# Arranged_in_Fusion.net
KiCad netlist of a schematic drawn in EAGLE
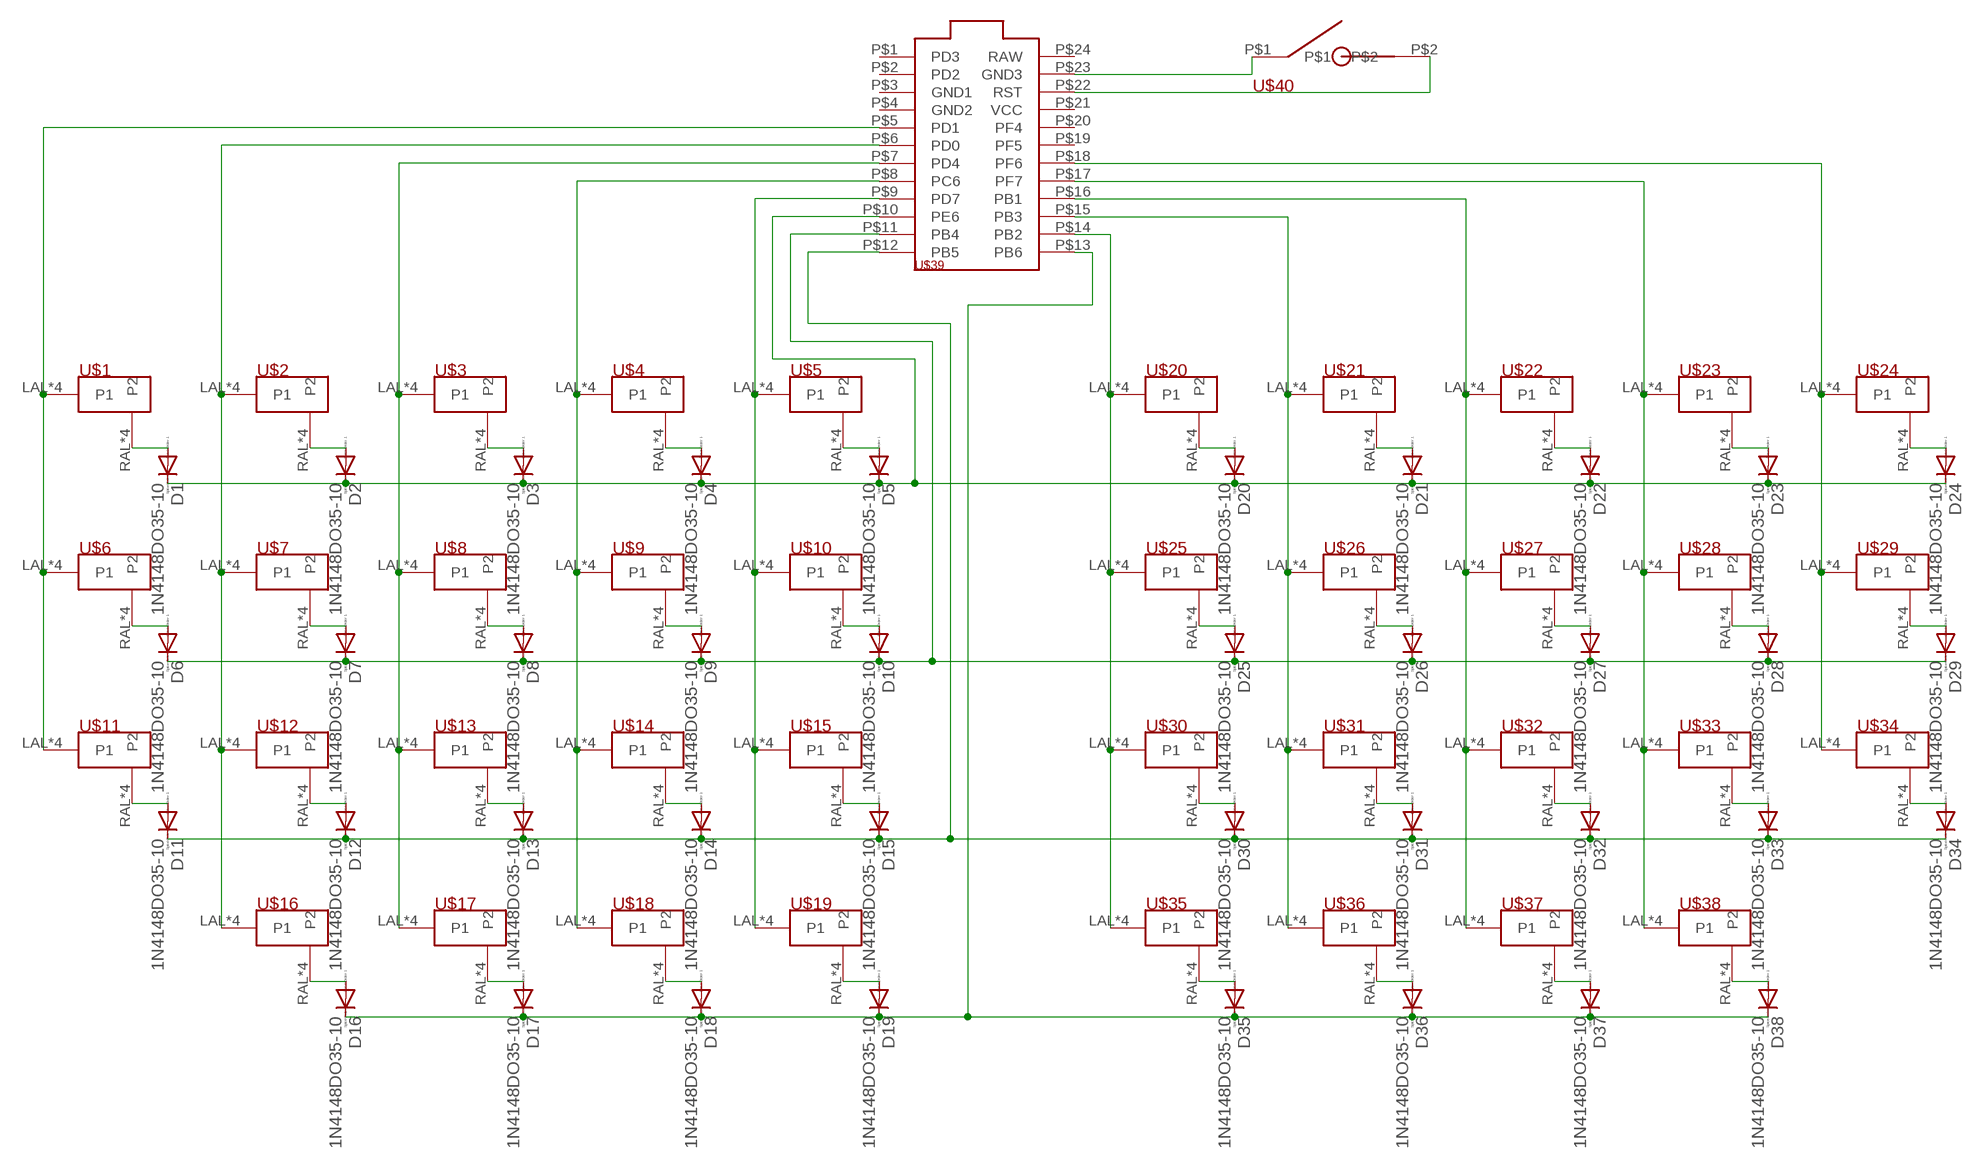
[diagram p0: schematic, sheet 1]

(export (version "E")
  (design (tool "Eeschema 10.0.6"))
  (components
    (comp (ref "D1")
      (value "1N4148DO35-10")
      (footprint "eagle-import:DO35-10")
      (libsource (lib "eagle-import") (part "1N4148DO35-10"))
    )
    (comp (ref "D2")
      (value "1N4148DO35-10")
      (footprint "eagle-import:DO35-10")
      (libsource (lib "eagle-import") (part "1N4148DO35-10"))
    )
    (comp (ref "D3")
      (value "1N4148DO35-10")
      (footprint "eagle-import:DO35-10")
      (libsource (lib "eagle-import") (part "1N4148DO35-10"))
    )
    (comp (ref "D4")
      (value "1N4148DO35-10")
      (footprint "eagle-import:DO35-10")
      (libsource (lib "eagle-import") (part "1N4148DO35-10"))
    )
    (comp (ref "D5")
      (value "1N4148DO35-10")
      (footprint "eagle-import:DO35-10")
      (libsource (lib "eagle-import") (part "1N4148DO35-10"))
    )
    (comp (ref "D6")
      (value "1N4148DO35-10")
      (footprint "eagle-import:DO35-10")
      (libsource (lib "eagle-import") (part "1N4148DO35-10"))
    )
    (comp (ref "D7")
      (value "1N4148DO35-10")
      (footprint "eagle-import:DO35-10")
      (libsource (lib "eagle-import") (part "1N4148DO35-10"))
    )
    (comp (ref "D8")
      (value "1N4148DO35-10")
      (footprint "eagle-import:DO35-10")
      (libsource (lib "eagle-import") (part "1N4148DO35-10"))
    )
    (comp (ref "D9")
      (value "1N4148DO35-10")
      (footprint "eagle-import:DO35-10")
      (libsource (lib "eagle-import") (part "1N4148DO35-10"))
    )
    (comp (ref "D10")
      (value "1N4148DO35-10")
      (footprint "eagle-import:DO35-10")
      (libsource (lib "eagle-import") (part "1N4148DO35-10"))
    )
    (comp (ref "D11")
      (value "1N4148DO35-10")
      (footprint "eagle-import:DO35-10")
      (libsource (lib "eagle-import") (part "1N4148DO35-10"))
    )
    (comp (ref "D12")
      (value "1N4148DO35-10")
      (footprint "eagle-import:DO35-10")
      (libsource (lib "eagle-import") (part "1N4148DO35-10"))
    )
    (comp (ref "D13")
      (value "1N4148DO35-10")
      (footprint "eagle-import:DO35-10")
      (libsource (lib "eagle-import") (part "1N4148DO35-10"))
    )
    (comp (ref "D14")
      (value "1N4148DO35-10")
      (footprint "eagle-import:DO35-10")
      (libsource (lib "eagle-import") (part "1N4148DO35-10"))
    )
    (comp (ref "D15")
      (value "1N4148DO35-10")
      (footprint "eagle-import:DO35-10")
      (libsource (lib "eagle-import") (part "1N4148DO35-10"))
    )
    (comp (ref "D16")
      (value "1N4148DO35-10")
      (footprint "eagle-import:DO35-10")
      (libsource (lib "eagle-import") (part "1N4148DO35-10"))
    )
    (comp (ref "D17")
      (value "1N4148DO35-10")
      (footprint "eagle-import:DO35-10")
      (libsource (lib "eagle-import") (part "1N4148DO35-10"))
    )
    (comp (ref "D18")
      (value "1N4148DO35-10")
      (footprint "eagle-import:DO35-10")
      (libsource (lib "eagle-import") (part "1N4148DO35-10"))
    )
    (comp (ref "D19")
      (value "1N4148DO35-10")
      (footprint "eagle-import:DO35-10")
      (libsource (lib "eagle-import") (part "1N4148DO35-10"))
    )
    (comp (ref "D20")
      (value "1N4148DO35-10")
      (footprint "eagle-import:DO35-10")
      (libsource (lib "eagle-import") (part "1N4148DO35-10"))
    )
    (comp (ref "D21")
      (value "1N4148DO35-10")
      (footprint "eagle-import:DO35-10")
      (libsource (lib "eagle-import") (part "1N4148DO35-10"))
    )
    (comp (ref "D22")
      (value "1N4148DO35-10")
      (footprint "eagle-import:DO35-10")
      (libsource (lib "eagle-import") (part "1N4148DO35-10"))
    )
    (comp (ref "D23")
      (value "1N4148DO35-10")
      (footprint "eagle-import:DO35-10")
      (libsource (lib "eagle-import") (part "1N4148DO35-10"))
    )
    (comp (ref "D24")
      (value "1N4148DO35-10")
      (footprint "eagle-import:DO35-10")
      (libsource (lib "eagle-import") (part "1N4148DO35-10"))
    )
    (comp (ref "D25")
      (value "1N4148DO35-10")
      (footprint "eagle-import:DO35-10")
      (libsource (lib "eagle-import") (part "1N4148DO35-10"))
    )
    (comp (ref "D26")
      (value "1N4148DO35-10")
      (footprint "eagle-import:DO35-10")
      (libsource (lib "eagle-import") (part "1N4148DO35-10"))
    )
    (comp (ref "D27")
      (value "1N4148DO35-10")
      (footprint "eagle-import:DO35-10")
      (libsource (lib "eagle-import") (part "1N4148DO35-10"))
    )
    (comp (ref "D28")
      (value "1N4148DO35-10")
      (footprint "eagle-import:DO35-10")
      (libsource (lib "eagle-import") (part "1N4148DO35-10"))
    )
    (comp (ref "D29")
      (value "1N4148DO35-10")
      (footprint "eagle-import:DO35-10")
      (libsource (lib "eagle-import") (part "1N4148DO35-10"))
    )
    (comp (ref "D30")
      (value "1N4148DO35-10")
      (footprint "eagle-import:DO35-10")
      (libsource (lib "eagle-import") (part "1N4148DO35-10"))
    )
    (comp (ref "D31")
      (value "1N4148DO35-10")
      (footprint "eagle-import:DO35-10")
      (libsource (lib "eagle-import") (part "1N4148DO35-10"))
    )
    (comp (ref "D32")
      (value "1N4148DO35-10")
      (footprint "eagle-import:DO35-10")
      (libsource (lib "eagle-import") (part "1N4148DO35-10"))
    )
    (comp (ref "D33")
      (value "1N4148DO35-10")
      (footprint "eagle-import:DO35-10")
      (libsource (lib "eagle-import") (part "1N4148DO35-10"))
    )
    (comp (ref "D34")
      (value "1N4148DO35-10")
      (footprint "eagle-import:DO35-10")
      (libsource (lib "eagle-import") (part "1N4148DO35-10"))
    )
    (comp (ref "D35")
      (value "1N4148DO35-10")
      (footprint "eagle-import:DO35-10")
      (libsource (lib "eagle-import") (part "1N4148DO35-10"))
    )
    (comp (ref "D36")
      (value "1N4148DO35-10")
      (footprint "eagle-import:DO35-10")
      (libsource (lib "eagle-import") (part "1N4148DO35-10"))
    )
    (comp (ref "D37")
      (value "1N4148DO35-10")
      (footprint "eagle-import:DO35-10")
      (libsource (lib "eagle-import") (part "1N4148DO35-10"))
    )
    (comp (ref "D38")
      (value "1N4148DO35-10")
      (footprint "eagle-import:DO35-10")
      (libsource (lib "eagle-import") (part "1N4148DO35-10"))
    )
    (comp (ref "U$1")
      (value "MANDOUBLEONESIDED")
      (footprint "eagle-import:MX_ALPS")
      (libsource (lib "eagle-import") (part "MANDOUBLEONESIDED"))
    )
    (comp (ref "U$2")
      (value "MANDOUBLEONESIDED")
      (footprint "eagle-import:MX_ALPS")
      (libsource (lib "eagle-import") (part "MANDOUBLEONESIDED"))
    )
    (comp (ref "U$3")
      (value "MANDOUBLEONESIDED")
      (footprint "eagle-import:MX_ALPS")
      (libsource (lib "eagle-import") (part "MANDOUBLEONESIDED"))
    )
    (comp (ref "U$4")
      (value "MANDOUBLEONESIDED")
      (footprint "eagle-import:MX_ALPS")
      (libsource (lib "eagle-import") (part "MANDOUBLEONESIDED"))
    )
    (comp (ref "U$5")
      (value "MANDOUBLEONESIDED")
      (footprint "eagle-import:MX_ALPS")
      (libsource (lib "eagle-import") (part "MANDOUBLEONESIDED"))
    )
    (comp (ref "U$6")
      (value "MANDOUBLEONESIDED")
      (footprint "eagle-import:MX_ALPS")
      (libsource (lib "eagle-import") (part "MANDOUBLEONESIDED"))
    )
    (comp (ref "U$7")
      (value "MANDOUBLEONESIDED")
      (footprint "eagle-import:MX_ALPS")
      (libsource (lib "eagle-import") (part "MANDOUBLEONESIDED"))
    )
    (comp (ref "U$8")
      (value "MANDOUBLEONESIDED")
      (footprint "eagle-import:MX_ALPS")
      (libsource (lib "eagle-import") (part "MANDOUBLEONESIDED"))
    )
    (comp (ref "U$9")
      (value "MANDOUBLEONESIDED")
      (footprint "eagle-import:MX_ALPS")
      (libsource (lib "eagle-import") (part "MANDOUBLEONESIDED"))
    )
    (comp (ref "U$10")
      (value "MANDOUBLEONESIDED")
      (footprint "eagle-import:MX_ALPS")
      (libsource (lib "eagle-import") (part "MANDOUBLEONESIDED"))
    )
    (comp (ref "U$11")
      (value "MANDOUBLEONESIDED")
      (footprint "eagle-import:MX_ALPS")
      (libsource (lib "eagle-import") (part "MANDOUBLEONESIDED"))
    )
    (comp (ref "U$12")
      (value "MANDOUBLEONESIDED")
      (footprint "eagle-import:MX_ALPS")
      (libsource (lib "eagle-import") (part "MANDOUBLEONESIDED"))
    )
    (comp (ref "U$13")
      (value "MANDOUBLEONESIDED")
      (footprint "eagle-import:MX_ALPS")
      (libsource (lib "eagle-import") (part "MANDOUBLEONESIDED"))
    )
    (comp (ref "U$14")
      (value "MANDOUBLEONESIDED")
      (footprint "eagle-import:MX_ALPS")
      (libsource (lib "eagle-import") (part "MANDOUBLEONESIDED"))
    )
    (comp (ref "U$15")
      (value "MANDOUBLEONESIDED")
      (footprint "eagle-import:MX_ALPS")
      (libsource (lib "eagle-import") (part "MANDOUBLEONESIDED"))
    )
    (comp (ref "U$16")
      (value "MANDOUBLEONESIDED")
      (footprint "eagle-import:MX_ALPS")
      (libsource (lib "eagle-import") (part "MANDOUBLEONESIDED"))
    )
    (comp (ref "U$17")
      (value "MANDOUBLEONESIDED")
      (footprint "eagle-import:MX_ALPS")
      (libsource (lib "eagle-import") (part "MANDOUBLEONESIDED"))
    )
    (comp (ref "U$18")
      (value "MANDOUBLEONESIDED")
      (footprint "eagle-import:MX_ALPS")
      (libsource (lib "eagle-import") (part "MANDOUBLEONESIDED"))
    )
    (comp (ref "U$19")
      (value "MANDOUBLEONESIDED")
      (footprint "eagle-import:MX_ALPS")
      (libsource (lib "eagle-import") (part "MANDOUBLEONESIDED"))
    )
    (comp (ref "U$20")
      (value "MANDOUBLEONESIDED")
      (footprint "eagle-import:MX_ALPS")
      (libsource (lib "eagle-import") (part "MANDOUBLEONESIDED"))
    )
    (comp (ref "U$21")
      (value "MANDOUBLEONESIDED")
      (footprint "eagle-import:MX_ALPS")
      (libsource (lib "eagle-import") (part "MANDOUBLEONESIDED"))
    )
    (comp (ref "U$22")
      (value "MANDOUBLEONESIDED")
      (footprint "eagle-import:MX_ALPS")
      (libsource (lib "eagle-import") (part "MANDOUBLEONESIDED"))
    )
    (comp (ref "U$23")
      (value "MANDOUBLEONESIDED")
      (footprint "eagle-import:MX_ALPS")
      (libsource (lib "eagle-import") (part "MANDOUBLEONESIDED"))
    )
    (comp (ref "U$24")
      (value "MANDOUBLEONESIDED")
      (footprint "eagle-import:MX_ALPS")
      (libsource (lib "eagle-import") (part "MANDOUBLEONESIDED"))
    )
    (comp (ref "U$25")
      (value "MANDOUBLEONESIDED")
      (footprint "eagle-import:MX_ALPS")
      (libsource (lib "eagle-import") (part "MANDOUBLEONESIDED"))
    )
    (comp (ref "U$26")
      (value "MANDOUBLEONESIDED")
      (footprint "eagle-import:MX_ALPS")
      (libsource (lib "eagle-import") (part "MANDOUBLEONESIDED"))
    )
    (comp (ref "U$27")
      (value "MANDOUBLEONESIDED")
      (footprint "eagle-import:MX_ALPS")
      (libsource (lib "eagle-import") (part "MANDOUBLEONESIDED"))
    )
    (comp (ref "U$28")
      (value "MANDOUBLEONESIDED")
      (footprint "eagle-import:MX_ALPS")
      (libsource (lib "eagle-import") (part "MANDOUBLEONESIDED"))
    )
    (comp (ref "U$29")
      (value "MANDOUBLEONESIDED")
      (footprint "eagle-import:MX_ALPS")
      (libsource (lib "eagle-import") (part "MANDOUBLEONESIDED"))
    )
    (comp (ref "U$30")
      (value "MANDOUBLEONESIDED")
      (footprint "eagle-import:MX_ALPS")
      (libsource (lib "eagle-import") (part "MANDOUBLEONESIDED"))
    )
    (comp (ref "U$31")
      (value "MANDOUBLEONESIDED")
      (footprint "eagle-import:MX_ALPS")
      (libsource (lib "eagle-import") (part "MANDOUBLEONESIDED"))
    )
    (comp (ref "U$32")
      (value "MANDOUBLEONESIDED")
      (footprint "eagle-import:MX_ALPS")
      (libsource (lib "eagle-import") (part "MANDOUBLEONESIDED"))
    )
    (comp (ref "U$33")
      (value "MANDOUBLEONESIDED")
      (footprint "eagle-import:MX_ALPS")
      (libsource (lib "eagle-import") (part "MANDOUBLEONESIDED"))
    )
    (comp (ref "U$34")
      (value "MANDOUBLEONESIDED")
      (footprint "eagle-import:MX_ALPS")
      (libsource (lib "eagle-import") (part "MANDOUBLEONESIDED"))
    )
    (comp (ref "U$35")
      (value "MANDOUBLEONESIDED")
      (footprint "eagle-import:MX_ALPS")
      (libsource (lib "eagle-import") (part "MANDOUBLEONESIDED"))
    )
    (comp (ref "U$36")
      (value "MANDOUBLEONESIDED")
      (footprint "eagle-import:MX_ALPS")
      (libsource (lib "eagle-import") (part "MANDOUBLEONESIDED"))
    )
    (comp (ref "U$37")
      (value "MANDOUBLEONESIDED")
      (footprint "eagle-import:MX_ALPS")
      (libsource (lib "eagle-import") (part "MANDOUBLEONESIDED"))
    )
    (comp (ref "U$38")
      (value "MANDOUBLEONESIDED")
      (footprint "eagle-import:MX_ALPS")
      (libsource (lib "eagle-import") (part "MANDOUBLEONESIDED"))
    )
    (comp (ref "U$39")
      (value "PROMICRO")
      (footprint "eagle-import:PROMICRO")
      (libsource (lib "eagle-import") (part "PROMICRO"))
    )
    (comp (ref "U$40")
      (value "RSTSW")
      (footprint "eagle-import:SKHL")
      (libsource (lib "eagle-import") (part "RSTSW"))
    )
  )
  (nets
    (net (code "1") (name "Net-(D1-PadA)") (class "Default")
      (node (ref "D1") (pin "A") (pinfunction "A_A") (pintype "passive"))
      (node (ref "U$1") (pin "RAL") (pinfunction "P2_RAL") (pintype "bidirectional"))
      (node (ref "U$1") (pin "RAR") (pinfunction "P2_RAR") (pintype "bidirectional"))
      (node (ref "U$1") (pin "RCL") (pinfunction "P2_RCL") (pintype "bidirectional"))
      (node (ref "U$1") (pin "RCR") (pinfunction "P2_RCR") (pintype "bidirectional"))
    )
    (net (code "2") (name "Net-(D2-PadA)") (class "Default")
      (node (ref "D2") (pin "A") (pinfunction "A_A") (pintype "passive"))
      (node (ref "U$2") (pin "RAL") (pinfunction "P2_RAL") (pintype "bidirectional"))
      (node (ref "U$2") (pin "RAR") (pinfunction "P2_RAR") (pintype "bidirectional"))
      (node (ref "U$2") (pin "RCL") (pinfunction "P2_RCL") (pintype "bidirectional"))
      (node (ref "U$2") (pin "RCR") (pinfunction "P2_RCR") (pintype "bidirectional"))
    )
    (net (code "3") (name "Net-(D3-PadA)") (class "Default")
      (node (ref "D3") (pin "A") (pinfunction "A_A") (pintype "passive"))
      (node (ref "U$3") (pin "RAL") (pinfunction "P2_RAL") (pintype "bidirectional"))
      (node (ref "U$3") (pin "RAR") (pinfunction "P2_RAR") (pintype "bidirectional"))
      (node (ref "U$3") (pin "RCL") (pinfunction "P2_RCL") (pintype "bidirectional"))
      (node (ref "U$3") (pin "RCR") (pinfunction "P2_RCR") (pintype "bidirectional"))
    )
    (net (code "4") (name "Net-(D4-PadA)") (class "Default")
      (node (ref "D4") (pin "A") (pinfunction "A_A") (pintype "passive"))
      (node (ref "U$4") (pin "RAL") (pinfunction "P2_RAL") (pintype "bidirectional"))
      (node (ref "U$4") (pin "RAR") (pinfunction "P2_RAR") (pintype "bidirectional"))
      (node (ref "U$4") (pin "RCL") (pinfunction "P2_RCL") (pintype "bidirectional"))
      (node (ref "U$4") (pin "RCR") (pinfunction "P2_RCR") (pintype "bidirectional"))
    )
    (net (code "5") (name "Net-(D5-PadA)") (class "Default")
      (node (ref "D5") (pin "A") (pinfunction "A_A") (pintype "passive"))
      (node (ref "U$5") (pin "RAL") (pinfunction "P2_RAL") (pintype "bidirectional"))
      (node (ref "U$5") (pin "RAR") (pinfunction "P2_RAR") (pintype "bidirectional"))
      (node (ref "U$5") (pin "RCL") (pinfunction "P2_RCL") (pintype "bidirectional"))
      (node (ref "U$5") (pin "RCR") (pinfunction "P2_RCR") (pintype "bidirectional"))
    )
    (net (code "6") (name "Net-(D6-PadA)") (class "Default")
      (node (ref "D6") (pin "A") (pinfunction "A_A") (pintype "passive"))
      (node (ref "U$6") (pin "RAL") (pinfunction "P2_RAL") (pintype "bidirectional"))
      (node (ref "U$6") (pin "RAR") (pinfunction "P2_RAR") (pintype "bidirectional"))
      (node (ref "U$6") (pin "RCL") (pinfunction "P2_RCL") (pintype "bidirectional"))
      (node (ref "U$6") (pin "RCR") (pinfunction "P2_RCR") (pintype "bidirectional"))
    )
    (net (code "7") (name "Net-(D7-PadA)") (class "Default")
      (node (ref "D7") (pin "A") (pinfunction "A_A") (pintype "passive"))
      (node (ref "U$7") (pin "RAL") (pinfunction "P2_RAL") (pintype "bidirectional"))
      (node (ref "U$7") (pin "RAR") (pinfunction "P2_RAR") (pintype "bidirectional"))
      (node (ref "U$7") (pin "RCL") (pinfunction "P2_RCL") (pintype "bidirectional"))
      (node (ref "U$7") (pin "RCR") (pinfunction "P2_RCR") (pintype "bidirectional"))
    )
    (net (code "8") (name "Net-(D8-PadA)") (class "Default")
      (node (ref "D8") (pin "A") (pinfunction "A_A") (pintype "passive"))
      (node (ref "U$8") (pin "RAL") (pinfunction "P2_RAL") (pintype "bidirectional"))
      (node (ref "U$8") (pin "RAR") (pinfunction "P2_RAR") (pintype "bidirectional"))
      (node (ref "U$8") (pin "RCL") (pinfunction "P2_RCL") (pintype "bidirectional"))
      (node (ref "U$8") (pin "RCR") (pinfunction "P2_RCR") (pintype "bidirectional"))
    )
    (net (code "9") (name "Net-(D9-PadA)") (class "Default")
      (node (ref "D9") (pin "A") (pinfunction "A_A") (pintype "passive"))
      (node (ref "U$9") (pin "RAL") (pinfunction "P2_RAL") (pintype "bidirectional"))
      (node (ref "U$9") (pin "RAR") (pinfunction "P2_RAR") (pintype "bidirectional"))
      (node (ref "U$9") (pin "RCL") (pinfunction "P2_RCL") (pintype "bidirectional"))
      (node (ref "U$9") (pin "RCR") (pinfunction "P2_RCR") (pintype "bidirectional"))
    )
    (net (code "10") (name "Net-(D10-PadA)") (class "Default")
      (node (ref "D10") (pin "A") (pinfunction "A_A") (pintype "passive"))
      (node (ref "U$10") (pin "RAL") (pinfunction "P2_RAL") (pintype "bidirectional"))
      (node (ref "U$10") (pin "RAR") (pinfunction "P2_RAR") (pintype "bidirectional"))
      (node (ref "U$10") (pin "RCL") (pinfunction "P2_RCL") (pintype "bidirectional"))
      (node (ref "U$10") (pin "RCR") (pinfunction "P2_RCR") (pintype "bidirectional"))
    )
    (net (code "11") (name "Net-(D11-PadA)") (class "Default")
      (node (ref "D11") (pin "A") (pinfunction "A_A") (pintype "passive"))
      (node (ref "U$11") (pin "RAL") (pinfunction "P2_RAL") (pintype "bidirectional"))
      (node (ref "U$11") (pin "RAR") (pinfunction "P2_RAR") (pintype "bidirectional"))
      (node (ref "U$11") (pin "RCL") (pinfunction "P2_RCL") (pintype "bidirectional"))
      (node (ref "U$11") (pin "RCR") (pinfunction "P2_RCR") (pintype "bidirectional"))
    )
    (net (code "12") (name "Net-(D12-PadA)") (class "Default")
      (node (ref "D12") (pin "A") (pinfunction "A_A") (pintype "passive"))
      (node (ref "U$12") (pin "RAL") (pinfunction "P2_RAL") (pintype "bidirectional"))
      (node (ref "U$12") (pin "RAR") (pinfunction "P2_RAR") (pintype "bidirectional"))
      (node (ref "U$12") (pin "RCL") (pinfunction "P2_RCL") (pintype "bidirectional"))
      (node (ref "U$12") (pin "RCR") (pinfunction "P2_RCR") (pintype "bidirectional"))
    )
    (net (code "13") (name "Net-(D13-PadA)") (class "Default")
      (node (ref "D13") (pin "A") (pinfunction "A_A") (pintype "passive"))
      (node (ref "U$13") (pin "RAL") (pinfunction "P2_RAL") (pintype "bidirectional"))
      (node (ref "U$13") (pin "RAR") (pinfunction "P2_RAR") (pintype "bidirectional"))
      (node (ref "U$13") (pin "RCL") (pinfunction "P2_RCL") (pintype "bidirectional"))
      (node (ref "U$13") (pin "RCR") (pinfunction "P2_RCR") (pintype "bidirectional"))
    )
    (net (code "14") (name "Net-(D14-PadA)") (class "Default")
      (node (ref "D14") (pin "A") (pinfunction "A_A") (pintype "passive"))
      (node (ref "U$14") (pin "RAL") (pinfunction "P2_RAL") (pintype "bidirectional"))
      (node (ref "U$14") (pin "RAR") (pinfunction "P2_RAR") (pintype "bidirectional"))
      (node (ref "U$14") (pin "RCL") (pinfunction "P2_RCL") (pintype "bidirectional"))
      (node (ref "U$14") (pin "RCR") (pinfunction "P2_RCR") (pintype "bidirectional"))
    )
    (net (code "15") (name "Net-(D15-PadA)") (class "Default")
      (node (ref "D15") (pin "A") (pinfunction "A_A") (pintype "passive"))
      (node (ref "U$15") (pin "RAL") (pinfunction "P2_RAL") (pintype "bidirectional"))
      (node (ref "U$15") (pin "RAR") (pinfunction "P2_RAR") (pintype "bidirectional"))
      (node (ref "U$15") (pin "RCL") (pinfunction "P2_RCL") (pintype "bidirectional"))
      (node (ref "U$15") (pin "RCR") (pinfunction "P2_RCR") (pintype "bidirectional"))
    )
    (net (code "16") (name "Net-(D16-PadA)") (class "Default")
      (node (ref "D16") (pin "A") (pinfunction "A_A") (pintype "passive"))
      (node (ref "U$16") (pin "RAL") (pinfunction "P2_RAL") (pintype "bidirectional"))
      (node (ref "U$16") (pin "RAR") (pinfunction "P2_RAR") (pintype "bidirectional"))
      (node (ref "U$16") (pin "RCL") (pinfunction "P2_RCL") (pintype "bidirectional"))
      (node (ref "U$16") (pin "RCR") (pinfunction "P2_RCR") (pintype "bidirectional"))
    )
    (net (code "17") (name "Net-(D17-PadA)") (class "Default")
      (node (ref "D17") (pin "A") (pinfunction "A_A") (pintype "passive"))
      (node (ref "U$17") (pin "RAL") (pinfunction "P2_RAL") (pintype "bidirectional"))
      (node (ref "U$17") (pin "RAR") (pinfunction "P2_RAR") (pintype "bidirectional"))
      (node (ref "U$17") (pin "RCL") (pinfunction "P2_RCL") (pintype "bidirectional"))
      (node (ref "U$17") (pin "RCR") (pinfunction "P2_RCR") (pintype "bidirectional"))
    )
    (net (code "18") (name "Net-(D18-PadA)") (class "Default")
      (node (ref "D18") (pin "A") (pinfunction "A_A") (pintype "passive"))
      (node (ref "U$18") (pin "RAL") (pinfunction "P2_RAL") (pintype "bidirectional"))
      (node (ref "U$18") (pin "RAR") (pinfunction "P2_RAR") (pintype "bidirectional"))
      (node (ref "U$18") (pin "RCL") (pinfunction "P2_RCL") (pintype "bidirectional"))
      (node (ref "U$18") (pin "RCR") (pinfunction "P2_RCR") (pintype "bidirectional"))
    )
    (net (code "19") (name "Net-(D19-PadA)") (class "Default")
      (node (ref "D19") (pin "A") (pinfunction "A_A") (pintype "passive"))
      (node (ref "U$19") (pin "RAL") (pinfunction "P2_RAL") (pintype "bidirectional"))
      (node (ref "U$19") (pin "RAR") (pinfunction "P2_RAR") (pintype "bidirectional"))
      (node (ref "U$19") (pin "RCL") (pinfunction "P2_RCL") (pintype "bidirectional"))
      (node (ref "U$19") (pin "RCR") (pinfunction "P2_RCR") (pintype "bidirectional"))
    )
    (net (code "20") (name "Net-(D20-PadA)") (class "Default")
      (node (ref "D20") (pin "A") (pinfunction "A_A") (pintype "passive"))
      (node (ref "U$20") (pin "RAL") (pinfunction "P2_RAL") (pintype "bidirectional"))
      (node (ref "U$20") (pin "RAR") (pinfunction "P2_RAR") (pintype "bidirectional"))
      (node (ref "U$20") (pin "RCL") (pinfunction "P2_RCL") (pintype "bidirectional"))
      (node (ref "U$20") (pin "RCR") (pinfunction "P2_RCR") (pintype "bidirectional"))
    )
    (net (code "21") (name "Net-(D21-PadA)") (class "Default")
      (node (ref "D21") (pin "A") (pinfunction "A_A") (pintype "passive"))
      (node (ref "U$21") (pin "RAL") (pinfunction "P2_RAL") (pintype "bidirectional"))
      (node (ref "U$21") (pin "RAR") (pinfunction "P2_RAR") (pintype "bidirectional"))
      (node (ref "U$21") (pin "RCL") (pinfunction "P2_RCL") (pintype "bidirectional"))
      (node (ref "U$21") (pin "RCR") (pinfunction "P2_RCR") (pintype "bidirectional"))
    )
    (net (code "22") (name "Net-(D22-PadA)") (class "Default")
      (node (ref "D22") (pin "A") (pinfunction "A_A") (pintype "passive"))
      (node (ref "U$22") (pin "RAL") (pinfunction "P2_RAL") (pintype "bidirectional"))
      (node (ref "U$22") (pin "RAR") (pinfunction "P2_RAR") (pintype "bidirectional"))
      (node (ref "U$22") (pin "RCL") (pinfunction "P2_RCL") (pintype "bidirectional"))
      (node (ref "U$22") (pin "RCR") (pinfunction "P2_RCR") (pintype "bidirectional"))
    )
    (net (code "23") (name "Net-(D23-PadA)") (class "Default")
      (node (ref "D23") (pin "A") (pinfunction "A_A") (pintype "passive"))
      (node (ref "U$23") (pin "RAL") (pinfunction "P2_RAL") (pintype "bidirectional"))
      (node (ref "U$23") (pin "RAR") (pinfunction "P2_RAR") (pintype "bidirectional"))
      (node (ref "U$23") (pin "RCL") (pinfunction "P2_RCL") (pintype "bidirectional"))
      (node (ref "U$23") (pin "RCR") (pinfunction "P2_RCR") (pintype "bidirectional"))
    )
    (net (code "24") (name "Net-(D24-PadA)") (class "Default")
      (node (ref "D24") (pin "A") (pinfunction "A_A") (pintype "passive"))
      (node (ref "U$24") (pin "RAL") (pinfunction "P2_RAL") (pintype "bidirectional"))
      (node (ref "U$24") (pin "RAR") (pinfunction "P2_RAR") (pintype "bidirectional"))
      (node (ref "U$24") (pin "RCL") (pinfunction "P2_RCL") (pintype "bidirectional"))
      (node (ref "U$24") (pin "RCR") (pinfunction "P2_RCR") (pintype "bidirectional"))
    )
    (net (code "25") (name "Net-(D25-PadA)") (class "Default")
      (node (ref "D25") (pin "A") (pinfunction "A_A") (pintype "passive"))
      (node (ref "U$25") (pin "RAL") (pinfunction "P2_RAL") (pintype "bidirectional"))
      (node (ref "U$25") (pin "RAR") (pinfunction "P2_RAR") (pintype "bidirectional"))
      (node (ref "U$25") (pin "RCL") (pinfunction "P2_RCL") (pintype "bidirectional"))
      (node (ref "U$25") (pin "RCR") (pinfunction "P2_RCR") (pintype "bidirectional"))
    )
    (net (code "26") (name "Net-(D26-PadA)") (class "Default")
      (node (ref "D26") (pin "A") (pinfunction "A_A") (pintype "passive"))
      (node (ref "U$26") (pin "RAL") (pinfunction "P2_RAL") (pintype "bidirectional"))
      (node (ref "U$26") (pin "RAR") (pinfunction "P2_RAR") (pintype "bidirectional"))
      (node (ref "U$26") (pin "RCL") (pinfunction "P2_RCL") (pintype "bidirectional"))
      (node (ref "U$26") (pin "RCR") (pinfunction "P2_RCR") (pintype "bidirectional"))
    )
    (net (code "27") (name "Net-(D27-PadA)") (class "Default")
      (node (ref "D27") (pin "A") (pinfunction "A_A") (pintype "passive"))
      (node (ref "U$27") (pin "RAL") (pinfunction "P2_RAL") (pintype "bidirectional"))
      (node (ref "U$27") (pin "RAR") (pinfunction "P2_RAR") (pintype "bidirectional"))
      (node (ref "U$27") (pin "RCL") (pinfunction "P2_RCL") (pintype "bidirectional"))
      (node (ref "U$27") (pin "RCR") (pinfunction "P2_RCR") (pintype "bidirectional"))
    )
    (net (code "28") (name "Net-(D28-PadA)") (class "Default")
      (node (ref "D28") (pin "A") (pinfunction "A_A") (pintype "passive"))
      (node (ref "U$28") (pin "RAL") (pinfunction "P2_RAL") (pintype "bidirectional"))
      (node (ref "U$28") (pin "RAR") (pinfunction "P2_RAR") (pintype "bidirectional"))
      (node (ref "U$28") (pin "RCL") (pinfunction "P2_RCL") (pintype "bidirectional"))
      (node (ref "U$28") (pin "RCR") (pinfunction "P2_RCR") (pintype "bidirectional"))
    )
    (net (code "29") (name "Net-(D29-PadA)") (class "Default")
      (node (ref "D29") (pin "A") (pinfunction "A_A") (pintype "passive"))
      (node (ref "U$29") (pin "RAL") (pinfunction "P2_RAL") (pintype "bidirectional"))
      (node (ref "U$29") (pin "RAR") (pinfunction "P2_RAR") (pintype "bidirectional"))
      (node (ref "U$29") (pin "RCL") (pinfunction "P2_RCL") (pintype "bidirectional"))
      (node (ref "U$29") (pin "RCR") (pinfunction "P2_RCR") (pintype "bidirectional"))
    )
    (net (code "30") (name "Net-(D30-PadA)") (class "Default")
      (node (ref "D30") (pin "A") (pinfunction "A_A") (pintype "passive"))
      (node (ref "U$30") (pin "RAL") (pinfunction "P2_RAL") (pintype "bidirectional"))
      (node (ref "U$30") (pin "RAR") (pinfunction "P2_RAR") (pintype "bidirectional"))
      (node (ref "U$30") (pin "RCL") (pinfunction "P2_RCL") (pintype "bidirectional"))
      (node (ref "U$30") (pin "RCR") (pinfunction "P2_RCR") (pintype "bidirectional"))
    )
    (net (code "31") (name "Net-(D31-PadA)") (class "Default")
      (node (ref "D31") (pin "A") (pinfunction "A_A") (pintype "passive"))
      (node (ref "U$31") (pin "RAL") (pinfunction "P2_RAL") (pintype "bidirectional"))
      (node (ref "U$31") (pin "RAR") (pinfunction "P2_RAR") (pintype "bidirectional"))
      (node (ref "U$31") (pin "RCL") (pinfunction "P2_RCL") (pintype "bidirectional"))
      (node (ref "U$31") (pin "RCR") (pinfunction "P2_RCR") (pintype "bidirectional"))
    )
    (net (code "32") (name "Net-(D32-PadA)") (class "Default")
      (node (ref "D32") (pin "A") (pinfunction "A_A") (pintype "passive"))
      (node (ref "U$32") (pin "RAL") (pinfunction "P2_RAL") (pintype "bidirectional"))
      (node (ref "U$32") (pin "RAR") (pinfunction "P2_RAR") (pintype "bidirectional"))
      (node (ref "U$32") (pin "RCL") (pinfunction "P2_RCL") (pintype "bidirectional"))
      (node (ref "U$32") (pin "RCR") (pinfunction "P2_RCR") (pintype "bidirectional"))
    )
    (net (code "33") (name "Net-(D33-PadA)") (class "Default")
      (node (ref "D33") (pin "A") (pinfunction "A_A") (pintype "passive"))
      (node (ref "U$33") (pin "RAL") (pinfunction "P2_RAL") (pintype "bidirectional"))
      (node (ref "U$33") (pin "RAR") (pinfunction "P2_RAR") (pintype "bidirectional"))
      (node (ref "U$33") (pin "RCL") (pinfunction "P2_RCL") (pintype "bidirectional"))
      (node (ref "U$33") (pin "RCR") (pinfunction "P2_RCR") (pintype "bidirectional"))
    )
    (net (code "34") (name "Net-(D34-PadA)") (class "Default")
      (node (ref "D34") (pin "A") (pinfunction "A_A") (pintype "passive"))
      (node (ref "U$34") (pin "RAL") (pinfunction "P2_RAL") (pintype "bidirectional"))
      (node (ref "U$34") (pin "RAR") (pinfunction "P2_RAR") (pintype "bidirectional"))
      (node (ref "U$34") (pin "RCL") (pinfunction "P2_RCL") (pintype "bidirectional"))
      (node (ref "U$34") (pin "RCR") (pinfunction "P2_RCR") (pintype "bidirectional"))
    )
    (net (code "35") (name "Net-(D35-PadA)") (class "Default")
      (node (ref "D35") (pin "A") (pinfunction "A_A") (pintype "passive"))
      (node (ref "U$35") (pin "RAL") (pinfunction "P2_RAL") (pintype "bidirectional"))
      (node (ref "U$35") (pin "RAR") (pinfunction "P2_RAR") (pintype "bidirectional"))
      (node (ref "U$35") (pin "RCL") (pinfunction "P2_RCL") (pintype "bidirectional"))
      (node (ref "U$35") (pin "RCR") (pinfunction "P2_RCR") (pintype "bidirectional"))
    )
    (net (code "36") (name "Net-(D36-PadA)") (class "Default")
      (node (ref "D36") (pin "A") (pinfunction "A_A") (pintype "passive"))
      (node (ref "U$36") (pin "RAL") (pinfunction "P2_RAL") (pintype "bidirectional"))
      (node (ref "U$36") (pin "RAR") (pinfunction "P2_RAR") (pintype "bidirectional"))
      (node (ref "U$36") (pin "RCL") (pinfunction "P2_RCL") (pintype "bidirectional"))
      (node (ref "U$36") (pin "RCR") (pinfunction "P2_RCR") (pintype "bidirectional"))
    )
    (net (code "37") (name "Net-(D37-PadA)") (class "Default")
      (node (ref "D37") (pin "A") (pinfunction "A_A") (pintype "passive"))
      (node (ref "U$37") (pin "RAL") (pinfunction "P2_RAL") (pintype "bidirectional"))
      (node (ref "U$37") (pin "RAR") (pinfunction "P2_RAR") (pintype "bidirectional"))
      (node (ref "U$37") (pin "RCL") (pinfunction "P2_RCL") (pintype "bidirectional"))
      (node (ref "U$37") (pin "RCR") (pinfunction "P2_RCR") (pintype "bidirectional"))
    )
    (net (code "38") (name "Net-(D38-PadA)") (class "Default")
      (node (ref "D38") (pin "A") (pinfunction "A_A") (pintype "passive"))
      (node (ref "U$38") (pin "RAL") (pinfunction "P2_RAL") (pintype "bidirectional"))
      (node (ref "U$38") (pin "RAR") (pinfunction "P2_RAR") (pintype "bidirectional"))
      (node (ref "U$38") (pin "RCL") (pinfunction "P2_RCL") (pintype "bidirectional"))
      (node (ref "U$38") (pin "RCR") (pinfunction "P2_RCR") (pintype "bidirectional"))
    )
    (net (code "39") (name "Net-(U$39-GND3)") (class "Default")
      (node (ref "U$39") (pin "P$23") (pinfunction "GND3_P$23") (pintype "bidirectional"))
      (node (ref "U$40") (pin "P$1") (pinfunction "P$1_P$1") (pintype "bidirectional"))
    )
    (net (code "40") (name "Net-(U$39-PB1)") (class "Default")
      (node (ref "U$22") (pin "LAL") (pinfunction "P1_LAL") (pintype "bidirectional"))
      (node (ref "U$22") (pin "LAR") (pinfunction "P1_LAR") (pintype "bidirectional"))
      (node (ref "U$22") (pin "LCL") (pinfunction "P1_LCL") (pintype "bidirectional"))
      (node (ref "U$22") (pin "LCR") (pinfunction "P1_LCR") (pintype "bidirectional"))
      (node (ref "U$27") (pin "LAL") (pinfunction "P1_LAL") (pintype "bidirectional"))
      (node (ref "U$27") (pin "LAR") (pinfunction "P1_LAR") (pintype "bidirectional"))
      (node (ref "U$27") (pin "LCL") (pinfunction "P1_LCL") (pintype "bidirectional"))
      (node (ref "U$27") (pin "LCR") (pinfunction "P1_LCR") (pintype "bidirectional"))
      (node (ref "U$32") (pin "LAL") (pinfunction "P1_LAL") (pintype "bidirectional"))
      (node (ref "U$32") (pin "LAR") (pinfunction "P1_LAR") (pintype "bidirectional"))
      (node (ref "U$32") (pin "LCL") (pinfunction "P1_LCL") (pintype "bidirectional"))
      (node (ref "U$32") (pin "LCR") (pinfunction "P1_LCR") (pintype "bidirectional"))
      (node (ref "U$37") (pin "LAL") (pinfunction "P1_LAL") (pintype "bidirectional"))
      (node (ref "U$37") (pin "LAR") (pinfunction "P1_LAR") (pintype "bidirectional"))
      (node (ref "U$37") (pin "LCL") (pinfunction "P1_LCL") (pintype "bidirectional"))
      (node (ref "U$37") (pin "LCR") (pinfunction "P1_LCR") (pintype "bidirectional"))
      (node (ref "U$39") (pin "P$16") (pinfunction "PB1_P$16") (pintype "bidirectional"))
    )
    (net (code "41") (name "Net-(U$39-PB2)") (class "Default")
      (node (ref "U$20") (pin "LAL") (pinfunction "P1_LAL") (pintype "bidirectional"))
      (node (ref "U$20") (pin "LAR") (pinfunction "P1_LAR") (pintype "bidirectional"))
      (node (ref "U$20") (pin "LCL") (pinfunction "P1_LCL") (pintype "bidirectional"))
      (node (ref "U$20") (pin "LCR") (pinfunction "P1_LCR") (pintype "bidirectional"))
      (node (ref "U$25") (pin "LAL") (pinfunction "P1_LAL") (pintype "bidirectional"))
      (node (ref "U$25") (pin "LAR") (pinfunction "P1_LAR") (pintype "bidirectional"))
      (node (ref "U$25") (pin "LCL") (pinfunction "P1_LCL") (pintype "bidirectional"))
      (node (ref "U$25") (pin "LCR") (pinfunction "P1_LCR") (pintype "bidirectional"))
      (node (ref "U$30") (pin "LAL") (pinfunction "P1_LAL") (pintype "bidirectional"))
      (node (ref "U$30") (pin "LAR") (pinfunction "P1_LAR") (pintype "bidirectional"))
      (node (ref "U$30") (pin "LCL") (pinfunction "P1_LCL") (pintype "bidirectional"))
      (node (ref "U$30") (pin "LCR") (pinfunction "P1_LCR") (pintype "bidirectional"))
      (node (ref "U$35") (pin "LAL") (pinfunction "P1_LAL") (pintype "bidirectional"))
      (node (ref "U$35") (pin "LAR") (pinfunction "P1_LAR") (pintype "bidirectional"))
      (node (ref "U$35") (pin "LCL") (pinfunction "P1_LCL") (pintype "bidirectional"))
      (node (ref "U$35") (pin "LCR") (pinfunction "P1_LCR") (pintype "bidirectional"))
      (node (ref "U$39") (pin "P$14") (pinfunction "PB2_P$14") (pintype "bidirectional"))
    )
    (net (code "42") (name "Net-(U$39-PB3)") (class "Default")
      (node (ref "U$21") (pin "LAL") (pinfunction "P1_LAL") (pintype "bidirectional"))
      (node (ref "U$21") (pin "LAR") (pinfunction "P1_LAR") (pintype "bidirectional"))
      (node (ref "U$21") (pin "LCL") (pinfunction "P1_LCL") (pintype "bidirectional"))
      (node (ref "U$21") (pin "LCR") (pinfunction "P1_LCR") (pintype "bidirectional"))
      (node (ref "U$26") (pin "LAL") (pinfunction "P1_LAL") (pintype "bidirectional"))
      (node (ref "U$26") (pin "LAR") (pinfunction "P1_LAR") (pintype "bidirectional"))
      (node (ref "U$26") (pin "LCL") (pinfunction "P1_LCL") (pintype "bidirectional"))
      (node (ref "U$26") (pin "LCR") (pinfunction "P1_LCR") (pintype "bidirectional"))
      (node (ref "U$31") (pin "LAL") (pinfunction "P1_LAL") (pintype "bidirectional"))
      (node (ref "U$31") (pin "LAR") (pinfunction "P1_LAR") (pintype "bidirectional"))
      (node (ref "U$31") (pin "LCL") (pinfunction "P1_LCL") (pintype "bidirectional"))
      (node (ref "U$31") (pin "LCR") (pinfunction "P1_LCR") (pintype "bidirectional"))
      (node (ref "U$36") (pin "LAL") (pinfunction "P1_LAL") (pintype "bidirectional"))
      (node (ref "U$36") (pin "LAR") (pinfunction "P1_LAR") (pintype "bidirectional"))
      (node (ref "U$36") (pin "LCL") (pinfunction "P1_LCL") (pintype "bidirectional"))
      (node (ref "U$36") (pin "LCR") (pinfunction "P1_LCR") (pintype "bidirectional"))
      (node (ref "U$39") (pin "P$15") (pinfunction "PB3_P$15") (pintype "bidirectional"))
    )
    (net (code "43") (name "Net-(U$39-PB4)") (class "Default")
      (node (ref "D10") (pin "C") (pinfunction "C_C") (pintype "passive"))
      (node (ref "D25") (pin "C") (pinfunction "C_C") (pintype "passive"))
      (node (ref "D26") (pin "C") (pinfunction "C_C") (pintype "passive"))
      (node (ref "D27") (pin "C") (pinfunction "C_C") (pintype "passive"))
      (node (ref "D28") (pin "C") (pinfunction "C_C") (pintype "passive"))
      (node (ref "D29") (pin "C") (pinfunction "C_C") (pintype "passive"))
      (node (ref "D6") (pin "C") (pinfunction "C_C") (pintype "passive"))
      (node (ref "D7") (pin "C") (pinfunction "C_C") (pintype "passive"))
      (node (ref "D8") (pin "C") (pinfunction "C_C") (pintype "passive"))
      (node (ref "D9") (pin "C") (pinfunction "C_C") (pintype "passive"))
      (node (ref "U$39") (pin "P$11") (pinfunction "PB4_P$11") (pintype "bidirectional"))
    )
    (net (code "44") (name "Net-(U$39-PB5)") (class "Default")
      (node (ref "D11") (pin "C") (pinfunction "C_C") (pintype "passive"))
      (node (ref "D12") (pin "C") (pinfunction "C_C") (pintype "passive"))
      (node (ref "D13") (pin "C") (pinfunction "C_C") (pintype "passive"))
      (node (ref "D14") (pin "C") (pinfunction "C_C") (pintype "passive"))
      (node (ref "D15") (pin "C") (pinfunction "C_C") (pintype "passive"))
      (node (ref "D30") (pin "C") (pinfunction "C_C") (pintype "passive"))
      (node (ref "D31") (pin "C") (pinfunction "C_C") (pintype "passive"))
      (node (ref "D32") (pin "C") (pinfunction "C_C") (pintype "passive"))
      (node (ref "D33") (pin "C") (pinfunction "C_C") (pintype "passive"))
      (node (ref "D34") (pin "C") (pinfunction "C_C") (pintype "passive"))
      (node (ref "U$39") (pin "P$12") (pinfunction "PB5_P$12") (pintype "bidirectional"))
    )
    (net (code "45") (name "Net-(U$39-PB6)") (class "Default")
      (node (ref "D16") (pin "C") (pinfunction "C_C") (pintype "passive"))
      (node (ref "D17") (pin "C") (pinfunction "C_C") (pintype "passive"))
      (node (ref "D18") (pin "C") (pinfunction "C_C") (pintype "passive"))
      (node (ref "D19") (pin "C") (pinfunction "C_C") (pintype "passive"))
      (node (ref "D35") (pin "C") (pinfunction "C_C") (pintype "passive"))
      (node (ref "D36") (pin "C") (pinfunction "C_C") (pintype "passive"))
      (node (ref "D37") (pin "C") (pinfunction "C_C") (pintype "passive"))
      (node (ref "D38") (pin "C") (pinfunction "C_C") (pintype "passive"))
      (node (ref "U$39") (pin "P$13") (pinfunction "PB6_P$13") (pintype "bidirectional"))
    )
    (net (code "46") (name "Net-(U$39-PC6)") (class "Default")
      (node (ref "U$14") (pin "LAL") (pinfunction "P1_LAL") (pintype "bidirectional"))
      (node (ref "U$14") (pin "LAR") (pinfunction "P1_LAR") (pintype "bidirectional"))
      (node (ref "U$14") (pin "LCL") (pinfunction "P1_LCL") (pintype "bidirectional"))
      (node (ref "U$14") (pin "LCR") (pinfunction "P1_LCR") (pintype "bidirectional"))
      (node (ref "U$18") (pin "LAL") (pinfunction "P1_LAL") (pintype "bidirectional"))
      (node (ref "U$18") (pin "LAR") (pinfunction "P1_LAR") (pintype "bidirectional"))
      (node (ref "U$18") (pin "LCL") (pinfunction "P1_LCL") (pintype "bidirectional"))
      (node (ref "U$18") (pin "LCR") (pinfunction "P1_LCR") (pintype "bidirectional"))
      (node (ref "U$39") (pin "P$8") (pinfunction "PC6_P$8") (pintype "bidirectional"))
      (node (ref "U$4") (pin "LAL") (pinfunction "P1_LAL") (pintype "bidirectional"))
      (node (ref "U$4") (pin "LAR") (pinfunction "P1_LAR") (pintype "bidirectional"))
      (node (ref "U$4") (pin "LCL") (pinfunction "P1_LCL") (pintype "bidirectional"))
      (node (ref "U$4") (pin "LCR") (pinfunction "P1_LCR") (pintype "bidirectional"))
      (node (ref "U$9") (pin "LAL") (pinfunction "P1_LAL") (pintype "bidirectional"))
      (node (ref "U$9") (pin "LAR") (pinfunction "P1_LAR") (pintype "bidirectional"))
      (node (ref "U$9") (pin "LCL") (pinfunction "P1_LCL") (pintype "bidirectional"))
      (node (ref "U$9") (pin "LCR") (pinfunction "P1_LCR") (pintype "bidirectional"))
    )
    (net (code "47") (name "Net-(U$39-PD0)") (class "Default")
      (node (ref "U$12") (pin "LAL") (pinfunction "P1_LAL") (pintype "bidirectional"))
      (node (ref "U$12") (pin "LAR") (pinfunction "P1_LAR") (pintype "bidirectional"))
      (node (ref "U$12") (pin "LCL") (pinfunction "P1_LCL") (pintype "bidirectional"))
      (node (ref "U$12") (pin "LCR") (pinfunction "P1_LCR") (pintype "bidirectional"))
      (node (ref "U$16") (pin "LAL") (pinfunction "P1_LAL") (pintype "bidirectional"))
      (node (ref "U$16") (pin "LAR") (pinfunction "P1_LAR") (pintype "bidirectional"))
      (node (ref "U$16") (pin "LCL") (pinfunction "P1_LCL") (pintype "bidirectional"))
      (node (ref "U$16") (pin "LCR") (pinfunction "P1_LCR") (pintype "bidirectional"))
      (node (ref "U$2") (pin "LAL") (pinfunction "P1_LAL") (pintype "bidirectional"))
      (node (ref "U$2") (pin "LAR") (pinfunction "P1_LAR") (pintype "bidirectional"))
      (node (ref "U$2") (pin "LCL") (pinfunction "P1_LCL") (pintype "bidirectional"))
      (node (ref "U$2") (pin "LCR") (pinfunction "P1_LCR") (pintype "bidirectional"))
      (node (ref "U$39") (pin "P$6") (pinfunction "PD0_P$6") (pintype "bidirectional"))
      (node (ref "U$7") (pin "LAL") (pinfunction "P1_LAL") (pintype "bidirectional"))
      (node (ref "U$7") (pin "LAR") (pinfunction "P1_LAR") (pintype "bidirectional"))
      (node (ref "U$7") (pin "LCL") (pinfunction "P1_LCL") (pintype "bidirectional"))
      (node (ref "U$7") (pin "LCR") (pinfunction "P1_LCR") (pintype "bidirectional"))
    )
    (net (code "48") (name "Net-(U$39-PD1)") (class "Default")
      (node (ref "U$1") (pin "LAL") (pinfunction "P1_LAL") (pintype "bidirectional"))
      (node (ref "U$1") (pin "LAR") (pinfunction "P1_LAR") (pintype "bidirectional"))
      (node (ref "U$1") (pin "LCL") (pinfunction "P1_LCL") (pintype "bidirectional"))
      (node (ref "U$1") (pin "LCR") (pinfunction "P1_LCR") (pintype "bidirectional"))
      (node (ref "U$11") (pin "LAL") (pinfunction "P1_LAL") (pintype "bidirectional"))
      (node (ref "U$11") (pin "LAR") (pinfunction "P1_LAR") (pintype "bidirectional"))
      (node (ref "U$11") (pin "LCL") (pinfunction "P1_LCL") (pintype "bidirectional"))
      (node (ref "U$11") (pin "LCR") (pinfunction "P1_LCR") (pintype "bidirectional"))
      (node (ref "U$39") (pin "P$5") (pinfunction "PD1_P$5") (pintype "bidirectional"))
      (node (ref "U$6") (pin "LAL") (pinfunction "P1_LAL") (pintype "bidirectional"))
      (node (ref "U$6") (pin "LAR") (pinfunction "P1_LAR") (pintype "bidirectional"))
      (node (ref "U$6") (pin "LCL") (pinfunction "P1_LCL") (pintype "bidirectional"))
      (node (ref "U$6") (pin "LCR") (pinfunction "P1_LCR") (pintype "bidirectional"))
    )
    (net (code "49") (name "Net-(U$39-PD4)") (class "Default")
      (node (ref "U$13") (pin "LAL") (pinfunction "P1_LAL") (pintype "bidirectional"))
      (node (ref "U$13") (pin "LAR") (pinfunction "P1_LAR") (pintype "bidirectional"))
      (node (ref "U$13") (pin "LCL") (pinfunction "P1_LCL") (pintype "bidirectional"))
      (node (ref "U$13") (pin "LCR") (pinfunction "P1_LCR") (pintype "bidirectional"))
      (node (ref "U$17") (pin "LAL") (pinfunction "P1_LAL") (pintype "bidirectional"))
      (node (ref "U$17") (pin "LAR") (pinfunction "P1_LAR") (pintype "bidirectional"))
      (node (ref "U$17") (pin "LCL") (pinfunction "P1_LCL") (pintype "bidirectional"))
      (node (ref "U$17") (pin "LCR") (pinfunction "P1_LCR") (pintype "bidirectional"))
      (node (ref "U$3") (pin "LAL") (pinfunction "P1_LAL") (pintype "bidirectional"))
      (node (ref "U$3") (pin "LAR") (pinfunction "P1_LAR") (pintype "bidirectional"))
      (node (ref "U$3") (pin "LCL") (pinfunction "P1_LCL") (pintype "bidirectional"))
      (node (ref "U$3") (pin "LCR") (pinfunction "P1_LCR") (pintype "bidirectional"))
      (node (ref "U$39") (pin "P$7") (pinfunction "PD4_P$7") (pintype "bidirectional"))
      (node (ref "U$8") (pin "LAL") (pinfunction "P1_LAL") (pintype "bidirectional"))
      (node (ref "U$8") (pin "LAR") (pinfunction "P1_LAR") (pintype "bidirectional"))
      (node (ref "U$8") (pin "LCL") (pinfunction "P1_LCL") (pintype "bidirectional"))
      (node (ref "U$8") (pin "LCR") (pinfunction "P1_LCR") (pintype "bidirectional"))
    )
    (net (code "50") (name "Net-(U$39-PD7)") (class "Default")
      (node (ref "U$10") (pin "LAL") (pinfunction "P1_LAL") (pintype "bidirectional"))
      (node (ref "U$10") (pin "LAR") (pinfunction "P1_LAR") (pintype "bidirectional"))
      (node (ref "U$10") (pin "LCL") (pinfunction "P1_LCL") (pintype "bidirectional"))
      (node (ref "U$10") (pin "LCR") (pinfunction "P1_LCR") (pintype "bidirectional"))
      (node (ref "U$15") (pin "LAL") (pinfunction "P1_LAL") (pintype "bidirectional"))
      (node (ref "U$15") (pin "LAR") (pinfunction "P1_LAR") (pintype "bidirectional"))
      (node (ref "U$15") (pin "LCL") (pinfunction "P1_LCL") (pintype "bidirectional"))
      (node (ref "U$15") (pin "LCR") (pinfunction "P1_LCR") (pintype "bidirectional"))
      (node (ref "U$19") (pin "LAL") (pinfunction "P1_LAL") (pintype "bidirectional"))
      (node (ref "U$19") (pin "LAR") (pinfunction "P1_LAR") (pintype "bidirectional"))
      (node (ref "U$19") (pin "LCL") (pinfunction "P1_LCL") (pintype "bidirectional"))
      (node (ref "U$19") (pin "LCR") (pinfunction "P1_LCR") (pintype "bidirectional"))
      (node (ref "U$39") (pin "P$9") (pinfunction "PD7_P$9") (pintype "bidirectional"))
      (node (ref "U$5") (pin "LAL") (pinfunction "P1_LAL") (pintype "bidirectional"))
      (node (ref "U$5") (pin "LAR") (pinfunction "P1_LAR") (pintype "bidirectional"))
      (node (ref "U$5") (pin "LCL") (pinfunction "P1_LCL") (pintype "bidirectional"))
      (node (ref "U$5") (pin "LCR") (pinfunction "P1_LCR") (pintype "bidirectional"))
    )
    (net (code "51") (name "Net-(U$39-PE6)") (class "Default")
      (node (ref "D1") (pin "C") (pinfunction "C_C") (pintype "passive"))
      (node (ref "D2") (pin "C") (pinfunction "C_C") (pintype "passive"))
      (node (ref "D20") (pin "C") (pinfunction "C_C") (pintype "passive"))
      (node (ref "D21") (pin "C") (pinfunction "C_C") (pintype "passive"))
      (node (ref "D22") (pin "C") (pinfunction "C_C") (pintype "passive"))
      (node (ref "D23") (pin "C") (pinfunction "C_C") (pintype "passive"))
      (node (ref "D24") (pin "C") (pinfunction "C_C") (pintype "passive"))
      (node (ref "D3") (pin "C") (pinfunction "C_C") (pintype "passive"))
      (node (ref "D4") (pin "C") (pinfunction "C_C") (pintype "passive"))
      (node (ref "D5") (pin "C") (pinfunction "C_C") (pintype "passive"))
      (node (ref "U$39") (pin "P$10") (pinfunction "PE6_P$10") (pintype "bidirectional"))
    )
    (net (code "52") (name "Net-(U$39-PF6)") (class "Default")
      (node (ref "U$24") (pin "LAL") (pinfunction "P1_LAL") (pintype "bidirectional"))
      (node (ref "U$24") (pin "LAR") (pinfunction "P1_LAR") (pintype "bidirectional"))
      (node (ref "U$24") (pin "LCL") (pinfunction "P1_LCL") (pintype "bidirectional"))
      (node (ref "U$24") (pin "LCR") (pinfunction "P1_LCR") (pintype "bidirectional"))
      (node (ref "U$29") (pin "LAL") (pinfunction "P1_LAL") (pintype "bidirectional"))
      (node (ref "U$29") (pin "LAR") (pinfunction "P1_LAR") (pintype "bidirectional"))
      (node (ref "U$29") (pin "LCL") (pinfunction "P1_LCL") (pintype "bidirectional"))
      (node (ref "U$29") (pin "LCR") (pinfunction "P1_LCR") (pintype "bidirectional"))
      (node (ref "U$34") (pin "LAL") (pinfunction "P1_LAL") (pintype "bidirectional"))
      (node (ref "U$34") (pin "LAR") (pinfunction "P1_LAR") (pintype "bidirectional"))
      (node (ref "U$34") (pin "LCL") (pinfunction "P1_LCL") (pintype "bidirectional"))
      (node (ref "U$34") (pin "LCR") (pinfunction "P1_LCR") (pintype "bidirectional"))
      (node (ref "U$39") (pin "P$18") (pinfunction "PF6_P$18") (pintype "bidirectional"))
    )
    (net (code "53") (name "Net-(U$39-PF7)") (class "Default")
      (node (ref "U$23") (pin "LAL") (pinfunction "P1_LAL") (pintype "bidirectional"))
      (node (ref "U$23") (pin "LAR") (pinfunction "P1_LAR") (pintype "bidirectional"))
      (node (ref "U$23") (pin "LCL") (pinfunction "P1_LCL") (pintype "bidirectional"))
      (node (ref "U$23") (pin "LCR") (pinfunction "P1_LCR") (pintype "bidirectional"))
      (node (ref "U$28") (pin "LAL") (pinfunction "P1_LAL") (pintype "bidirectional"))
      (node (ref "U$28") (pin "LAR") (pinfunction "P1_LAR") (pintype "bidirectional"))
      (node (ref "U$28") (pin "LCL") (pinfunction "P1_LCL") (pintype "bidirectional"))
      (node (ref "U$28") (pin "LCR") (pinfunction "P1_LCR") (pintype "bidirectional"))
      (node (ref "U$33") (pin "LAL") (pinfunction "P1_LAL") (pintype "bidirectional"))
      (node (ref "U$33") (pin "LAR") (pinfunction "P1_LAR") (pintype "bidirectional"))
      (node (ref "U$33") (pin "LCL") (pinfunction "P1_LCL") (pintype "bidirectional"))
      (node (ref "U$33") (pin "LCR") (pinfunction "P1_LCR") (pintype "bidirectional"))
      (node (ref "U$38") (pin "LAL") (pinfunction "P1_LAL") (pintype "bidirectional"))
      (node (ref "U$38") (pin "LAR") (pinfunction "P1_LAR") (pintype "bidirectional"))
      (node (ref "U$38") (pin "LCL") (pinfunction "P1_LCL") (pintype "bidirectional"))
      (node (ref "U$38") (pin "LCR") (pinfunction "P1_LCR") (pintype "bidirectional"))
      (node (ref "U$39") (pin "P$17") (pinfunction "PF7_P$17") (pintype "bidirectional"))
    )
    (net (code "54") (name "Net-(U$39-RST)") (class "Default")
      (node (ref "U$39") (pin "P$22") (pinfunction "RST_P$22") (pintype "bidirectional"))
      (node (ref "U$40") (pin "P$2") (pinfunction "P$2_P$2") (pintype "bidirectional"))
    )
    (net (code "55") (name "unconnected-(U$39-GND1-PadP$3)") (class "Default")
      (node (ref "U$39") (pin "P$3") (pinfunction "GND1_P$3") (pintype "bidirectional"))
    )
    (net (code "56") (name "unconnected-(U$39-GND2-PadP$4)") (class "Default")
      (node (ref "U$39") (pin "P$4") (pinfunction "GND2_P$4") (pintype "bidirectional"))
    )
    (net (code "57") (name "unconnected-(U$39-PD2-PadP$2)") (class "Default")
      (node (ref "U$39") (pin "P$2") (pinfunction "PD2_P$2") (pintype "bidirectional"))
    )
    (net (code "58") (name "unconnected-(U$39-PD3-PadP$1)") (class "Default")
      (node (ref "U$39") (pin "P$1") (pinfunction "PD3_P$1") (pintype "bidirectional"))
    )
    (net (code "59") (name "unconnected-(U$39-PF4-PadP$20)") (class "Default")
      (node (ref "U$39") (pin "P$20") (pinfunction "PF4_P$20") (pintype "bidirectional"))
    )
    (net (code "60") (name "unconnected-(U$39-PF5-PadP$19)") (class "Default")
      (node (ref "U$39") (pin "P$19") (pinfunction "PF5_P$19") (pintype "bidirectional"))
    )
    (net (code "61") (name "unconnected-(U$39-RAW-PadP$24)") (class "Default")
      (node (ref "U$39") (pin "P$24") (pinfunction "RAW_P$24") (pintype "bidirectional"))
    )
    (net (code "62") (name "unconnected-(U$39-VCC-PadP$21)") (class "Default")
      (node (ref "U$39") (pin "P$21") (pinfunction "VCC_P$21") (pintype "bidirectional"))
    )
  )
)
